# RC_car.net
KiCad netlist of a schematic drawn in EAGLE
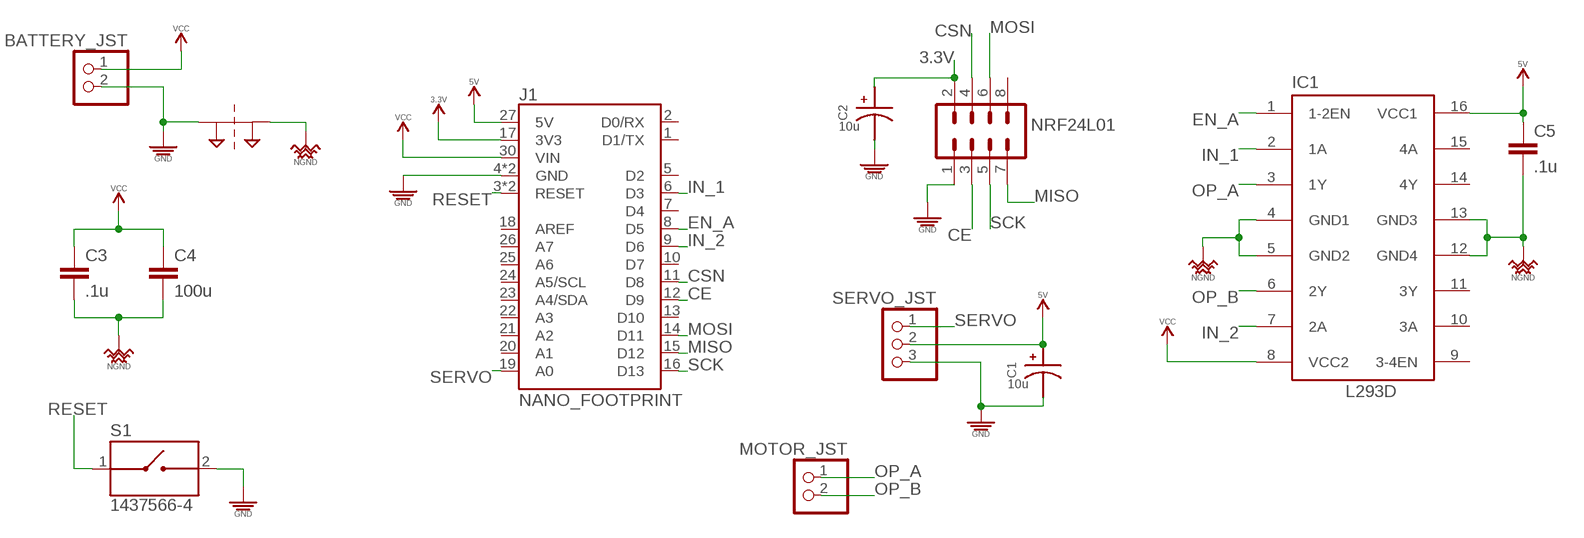
[diagram p0: schematic, sheet 1]

(export (version "E")
  (design (tool "Eeschema 10.0.6"))
  (components
    (comp (ref "BATTERY_JST")
      (value "PINHD-1X2")
      (footprint "eagle-import:1X02")
      (libsource (lib "eagle-import") (part "PINHD-1X2"))
    )
    (comp (ref "C1")
      (value "10u")
      (footprint "eagle-import:CAPPRD200W50D550H1250")
      (fields
        (field (name "DIGI-KEY_PART_NUMBER") "UVR1E100MDD1TA-ND")
        (field (name "MF") "Nichicon")
        (field (name "MP") "UVR1E100MDD")
      )
      (libsource (lib "eagle-import") (part "UVR1E100MDD"))
    )
    (comp (ref "C2")
      (value "10u")
      (footprint "eagle-import:CAPPRD200W50D550H1250")
      (fields
        (field (name "DIGI-KEY_PART_NUMBER") "UVR1E100MDD1TA-ND")
        (field (name "MF") "Nichicon")
        (field (name "MP") "UVR1E100MDD")
      )
      (libsource (lib "eagle-import") (part "UVR1E100MDD"))
    )
    (comp (ref "C3")
      (value ".1u")
      (footprint "eagle-import:C2.5-3")
      (libsource (lib "eagle-import") (part "C2,5-3"))
    )
    (comp (ref "C4")
      (value "100u")
      (footprint "eagle-import:C2.5-3")
      (libsource (lib "eagle-import") (part "C2,5-3"))
    )
    (comp (ref "C5")
      (value ".1u")
      (footprint "eagle-import:C2.5-3")
      (libsource (lib "eagle-import") (part "C2,5-3"))
    )
    (comp (ref "IC1")
      (value "L293D")
      (footprint "eagle-import:DIL16")
      (libsource (lib "eagle-import") (part "L293D"))
    )
    (comp (ref "J1")
      (value "NANO_FOOTPRINT")
      (footprint "eagle-import:NANO")
      (libsource (lib "eagle-import") (part "NANO_FOOTPRINT"))
    )
    (comp (ref "MOTOR_JST")
      (value "PINHD-1X2")
      (footprint "eagle-import:1X02")
      (libsource (lib "eagle-import") (part "PINHD-1X2"))
    )
    (comp (ref "NET_BRIDGE1")
      (value "NET_BRIDGE")
      (footprint "eagle-import:NET_BRIDGE")
      (libsource (lib "eagle-import") (part "NET_BRIDGE"))
    )
    (comp (ref "NRF24L01")
      (value "MA04-2")
      (footprint "eagle-import:MA04-2")
      (libsource (lib "eagle-import") (part "MA04-2"))
    )
    (comp (ref "S1")
      (value "1437566-4")
      (footprint "eagle-import:SW_1437566-4")
      (fields
        (field (name "DIGI-KEY_PART_NUMBER") "2266-1437566-4TR-ND")
        (field (name "MF") "TE Connectivity")
      )
      (libsource (lib "eagle-import") (part "1437566-4"))
    )
    (comp (ref "SERVO_JST")
      (value "PINHD-1X3")
      (footprint "eagle-import:1X03")
      (libsource (lib "eagle-import") (part "PINHD-1X3"))
    )
  )
  (nets
    (net (code "1") (name "/CE") (class "Default")
      (node (ref "J1") (pin "12") (pinfunction "D9_12") (pintype "bidirectional"))
      (node (ref "NRF24L01") (pin "3") (pinfunction "3_3") (pintype "passive"))
    )
    (net (code "2") (name "/CSN") (class "Default")
      (node (ref "J1") (pin "11") (pinfunction "D8_11") (pintype "bidirectional"))
      (node (ref "NRF24L01") (pin "4") (pinfunction "4_4") (pintype "passive"))
    )
    (net (code "3") (name "/EN_A") (class "Default")
      (node (ref "IC1") (pin "1") (pinfunction "1-2EN_1") (pintype "input"))
      (node (ref "J1") (pin "8") (pinfunction "D5_8") (pintype "bidirectional"))
    )
    (net (code "4") (name "/IN_1") (class "Default")
      (node (ref "IC1") (pin "2") (pinfunction "1A_2") (pintype "input"))
      (node (ref "J1") (pin "6") (pinfunction "D3_6") (pintype "bidirectional"))
    )
    (net (code "5") (name "/IN_2") (class "Default")
      (node (ref "IC1") (pin "7") (pinfunction "2A_7") (pintype "input"))
      (node (ref "J1") (pin "9") (pinfunction "D6_9") (pintype "bidirectional"))
    )
    (net (code "6") (name "/MISO") (class "Default")
      (node (ref "J1") (pin "15") (pinfunction "D12_15") (pintype "bidirectional"))
      (node (ref "NRF24L01") (pin "7") (pinfunction "7_7") (pintype "passive"))
    )
    (net (code "7") (name "/MOSI") (class "Default")
      (node (ref "J1") (pin "14") (pinfunction "D11_14") (pintype "bidirectional"))
      (node (ref "NRF24L01") (pin "6") (pinfunction "6_6") (pintype "passive"))
    )
    (net (code "8") (name "/OP_A") (class "Default")
      (node (ref "IC1") (pin "3") (pinfunction "1Y_3") (pintype "output"))
      (node (ref "MOTOR_JST") (pin "1") (pinfunction "1_1") (pintype "passive"))
    )
    (net (code "9") (name "/OP_B") (class "Default")
      (node (ref "IC1") (pin "6") (pinfunction "2Y_6") (pintype "output"))
      (node (ref "MOTOR_JST") (pin "2") (pinfunction "2_2") (pintype "passive"))
    )
    (net (code "10") (name "/RESET") (class "Default")
      (node (ref "J1") (pin "28") (pinfunction "RESET_28") (pintype "bidirectional"))
      (node (ref "J1") (pin "3") (pinfunction "RESET_3") (pintype "bidirectional"))
      (node (ref "S1") (pin "1") (pinfunction "1_1") (pintype "passive"))
    )
    (net (code "11") (name "/SCK") (class "Default")
      (node (ref "J1") (pin "16") (pinfunction "D13_16") (pintype "bidirectional"))
      (node (ref "NRF24L01") (pin "5") (pinfunction "5_5") (pintype "passive"))
    )
    (net (code "12") (name "/SERVO") (class "Default")
      (node (ref "J1") (pin "19") (pinfunction "A0_19") (pintype "bidirectional"))
      (node (ref "SERVO_JST") (pin "1") (pinfunction "1_1") (pintype "passive"))
    )
    (net (code "13") (name "3.3V") (class "Default")
      (node (ref "C2") (pin "1") (pinfunction "1_1") (pintype "passive"))
      (node (ref "J1") (pin "17") (pinfunction "3V3_17") (pintype "bidirectional"))
      (node (ref "NRF24L01") (pin "2") (pinfunction "2_2") (pintype "passive"))
    )
    (net (code "14") (name "5V") (class "Default")
      (node (ref "C1") (pin "1") (pinfunction "1_1") (pintype "passive"))
      (node (ref "C5") (pin "1") (pinfunction "1_1") (pintype "passive"))
      (node (ref "IC1") (pin "16") (pinfunction "VCC1_16") (pintype "power_in"))
      (node (ref "J1") (pin "27") (pinfunction "5V_27") (pintype "bidirectional"))
      (node (ref "SERVO_JST") (pin "2") (pinfunction "2_2") (pintype "passive"))
    )
    (net (code "15") (name "GND") (class "Default")
      (node (ref "BATTERY_JST") (pin "2") (pinfunction "2_2") (pintype "passive"))
      (node (ref "C1") (pin "2") (pinfunction "2_2") (pintype "passive"))
      (node (ref "C2") (pin "2") (pinfunction "2_2") (pintype "passive"))
      (node (ref "J1") (pin "29") (pinfunction "GND_29") (pintype "bidirectional"))
      (node (ref "J1") (pin "4") (pinfunction "GND_4") (pintype "bidirectional"))
      (node (ref "NET_BRIDGE1") (pin "P$1") (pinfunction "P$1_P$1") (pintype "passive"))
      (node (ref "NRF24L01") (pin "1") (pinfunction "1_1") (pintype "passive"))
      (node (ref "S1") (pin "2") (pinfunction "2_2") (pintype "passive"))
      (node (ref "SERVO_JST") (pin "3") (pinfunction "3_3") (pintype "passive"))
    )
    (net (code "16") (name "NGND") (class "Default")
      (node (ref "C3") (pin "2") (pinfunction "2_2") (pintype "passive"))
      (node (ref "C4") (pin "2") (pinfunction "2_2") (pintype "passive"))
      (node (ref "C5") (pin "2") (pinfunction "2_2") (pintype "passive"))
      (node (ref "IC1") (pin "12") (pinfunction "GND4_12") (pintype "power_in"))
      (node (ref "IC1") (pin "13") (pinfunction "GND3_13") (pintype "power_in"))
      (node (ref "IC1") (pin "4") (pinfunction "GND1_4") (pintype "power_in"))
      (node (ref "IC1") (pin "5") (pinfunction "GND2_5") (pintype "power_in"))
      (node (ref "NET_BRIDGE1") (pin "P$2") (pinfunction "P$2_P$2") (pintype "passive"))
    )
    (net (code "17") (name "VCC") (class "Default")
      (node (ref "BATTERY_JST") (pin "1") (pinfunction "1_1") (pintype "passive"))
      (node (ref "C3") (pin "1") (pinfunction "1_1") (pintype "passive"))
      (node (ref "C4") (pin "1") (pinfunction "1_1") (pintype "passive"))
      (node (ref "IC1") (pin "8") (pinfunction "VCC2_8") (pintype "power_in"))
      (node (ref "J1") (pin "30") (pinfunction "VIN_30") (pintype "bidirectional"))
    )
    (net (code "18") (name "unconnected-(IC1-3-4EN-Pad9)") (class "Default")
      (node (ref "IC1") (pin "9") (pinfunction "3-4EN_9") (pintype "input"))
    )
    (net (code "19") (name "unconnected-(IC1-3A-Pad10)") (class "Default")
      (node (ref "IC1") (pin "10") (pinfunction "3A_10") (pintype "input"))
    )
    (net (code "20") (name "unconnected-(IC1-3Y-Pad11)") (class "Default")
      (node (ref "IC1") (pin "11") (pinfunction "3Y_11") (pintype "output"))
    )
    (net (code "21") (name "unconnected-(IC1-4A-Pad15)") (class "Default")
      (node (ref "IC1") (pin "15") (pinfunction "4A_15") (pintype "input"))
    )
    (net (code "22") (name "unconnected-(IC1-4Y-Pad14)") (class "Default")
      (node (ref "IC1") (pin "14") (pinfunction "4Y_14") (pintype "output"))
    )
    (net (code "23") (name "unconnected-(J1-A1-Pad20)") (class "Default")
      (node (ref "J1") (pin "20") (pinfunction "A1_20") (pintype "bidirectional"))
    )
    (net (code "24") (name "unconnected-(J1-A2-Pad21)") (class "Default")
      (node (ref "J1") (pin "21") (pinfunction "A2_21") (pintype "bidirectional"))
    )
    (net (code "25") (name "unconnected-(J1-A3-Pad22)") (class "Default")
      (node (ref "J1") (pin "22") (pinfunction "A3_22") (pintype "bidirectional"))
    )
    (net (code "26") (name "unconnected-(J1-A4{slash}SDA-Pad23)") (class "Default")
      (node (ref "J1") (pin "23") (pinfunction "A4/SDA_23") (pintype "bidirectional"))
    )
    (net (code "27") (name "unconnected-(J1-A5{slash}SCL-Pad24)") (class "Default")
      (node (ref "J1") (pin "24") (pinfunction "A5/SCL_24") (pintype "bidirectional"))
    )
    (net (code "28") (name "unconnected-(J1-A6-Pad25)") (class "Default")
      (node (ref "J1") (pin "25") (pinfunction "A6_25") (pintype "bidirectional"))
    )
    (net (code "29") (name "unconnected-(J1-A7-Pad26)") (class "Default")
      (node (ref "J1") (pin "26") (pinfunction "A7_26") (pintype "bidirectional"))
    )
    (net (code "30") (name "unconnected-(J1-AREF-Pad18)") (class "Default")
      (node (ref "J1") (pin "18") (pinfunction "AREF_18") (pintype "bidirectional"))
    )
    (net (code "31") (name "unconnected-(J1-D0{slash}RX-Pad2)") (class "Default")
      (node (ref "J1") (pin "2") (pinfunction "D0/RX_2") (pintype "bidirectional"))
    )
    (net (code "32") (name "unconnected-(J1-D1{slash}TX-Pad1)") (class "Default")
      (node (ref "J1") (pin "1") (pinfunction "D1/TX_1") (pintype "bidirectional"))
    )
    (net (code "33") (name "unconnected-(J1-D2-Pad5)") (class "Default")
      (node (ref "J1") (pin "5") (pinfunction "D2_5") (pintype "bidirectional"))
    )
    (net (code "34") (name "unconnected-(J1-D4-Pad7)") (class "Default")
      (node (ref "J1") (pin "7") (pinfunction "D4_7") (pintype "bidirectional"))
    )
    (net (code "35") (name "unconnected-(J1-D7-Pad10)") (class "Default")
      (node (ref "J1") (pin "10") (pinfunction "D7_10") (pintype "bidirectional"))
    )
    (net (code "36") (name "unconnected-(J1-D10-Pad13)") (class "Default")
      (node (ref "J1") (pin "13") (pinfunction "D10_13") (pintype "bidirectional"))
    )
    (net (code "37") (name "unconnected-(NRF24L01-Pad8)") (class "Default")
      (node (ref "NRF24L01") (pin "8") (pinfunction "8_8") (pintype "passive"))
    )
  )
)
